# Opamp.net
KiCad netlist of a schematic drawn in Altium Designer
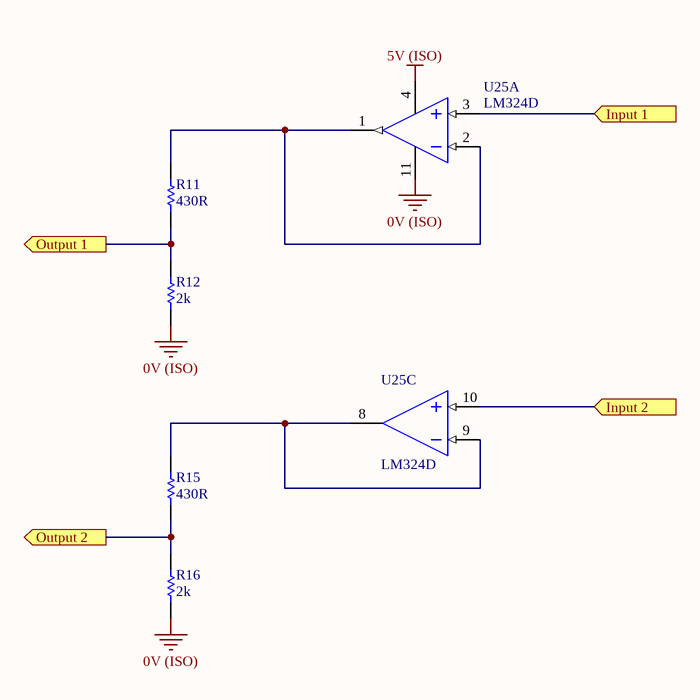
[diagram p0: Opamp.SchDoc]

(export (version "E")
  (design (tool "Eeschema 10.0.6"))
  (components
    (comp (ref "R11")
      (value "430R")
      (footprint "0805")
      (fields
        (field (name "MANUFACTURER") "YAGEO")
        (field (name "PART NUMBER") "RC0805FR07430RL")
        (field (name "TOLERANCE") "0.01")
      )
      (libsource (lib "ts_19-standard-library") (part "Resistor"))
    )
    (comp (ref "R12")
      (value "2k")
      (footprint "0805")
      (fields
        (field (name "MANUFACTURER") "YAGEO")
        (field (name "PART NUMBER") "RC0805FR072KL")
        (field (name "TOLERANCE") "0.01")
      )
      (libsource (lib "ts_19-standard-library") (part "Resistor"))
    )
    (comp (ref "R15")
      (value "430R")
      (footprint "0805")
      (fields
        (field (name "MANUFACTURER") "YAGEO")
        (field (name "PART NUMBER") "RC0805FR07430RL")
        (field (name "TOLERANCE") "0.01")
      )
      (libsource (lib "ts_19-standard-library") (part "Resistor"))
    )
    (comp (ref "R16")
      (value "2k")
      (footprint "0805")
      (fields
        (field (name "MANUFACTURER") "YAGEO")
        (field (name "PART NUMBER") "RC0805FR072KL")
        (field (name "TOLERANCE") "0.01")
      )
      (libsource (lib "ts_19-standard-library") (part "Resistor"))
    )
    (comp (ref "U25")
      (value "LM324D")
      (footprint "TI 14-SOIC")
      (description "IC OPAMP GP 4 CIRCUIT 14SOIC")
      (fields
        (field (name "MANUFACTURER") "Texas Instruments")
        (field (name "DIGIKEY PART NUMBER") "296-1390-5-ND")
      )
      (libsource (lib "ts_19-standard-library") (part "LM324D"))
    )
  )
  (nets
    (net (code "1") (name "/Input 1") (class "Default")
      (node (ref "U25") (pin "3") (pinfunction "1IN+_3") (pintype "input"))
    )
    (net (code "2") (name "/Input 2") (class "Default")
      (node (ref "U25") (pin "10") (pinfunction "3IN+_10") (pintype "input"))
    )
    (net (code "3") (name "/Output 1") (class "Default")
      (node (ref "R11") (pin "1") (pinfunction "1_1") (pintype "passive"))
      (node (ref "R12") (pin "2") (pinfunction "2_2") (pintype "passive"))
    )
    (net (code "4") (name "/Output 2") (class "Default")
      (node (ref "R15") (pin "1") (pinfunction "1_1") (pintype "passive"))
      (node (ref "R16") (pin "2") (pinfunction "2_2") (pintype "passive"))
    )
    (net (code "5") (name "0V (ISO)") (class "Default")
      (node (ref "R12") (pin "1") (pinfunction "1_1") (pintype "passive"))
      (node (ref "R16") (pin "1") (pinfunction "1_1") (pintype "passive"))
      (node (ref "U25") (pin "11") (pinfunction "GND_11") (pintype "power_in"))
    )
    (net (code "6") (name "5V (ISO)") (class "Default")
      (node (ref "U25") (pin "4") (pinfunction "VCC_4") (pintype "power_in"))
    )
    (net (code "7") (name "Net-(U25A-1OUT)") (class "Default")
      (node (ref "R11") (pin "2") (pinfunction "2_2") (pintype "passive"))
      (node (ref "U25") (pin "1") (pinfunction "1OUT_1") (pintype "output"))
      (node (ref "U25") (pin "2") (pinfunction "1IN+_2") (pintype "input"))
    )
    (net (code "8") (name "Net-(U25C-3IN-)") (class "Default")
      (node (ref "R15") (pin "2") (pinfunction "2_2") (pintype "passive"))
      (node (ref "U25") (pin "8") (pinfunction "3OUT_8") (pintype "passive"))
      (node (ref "U25") (pin "9") (pinfunction "3IN-_9") (pintype "input"))
    )
  )
)
